# opdracht_1_555_timer.net
KiCad netlist of a schematic drawn in EAGLE
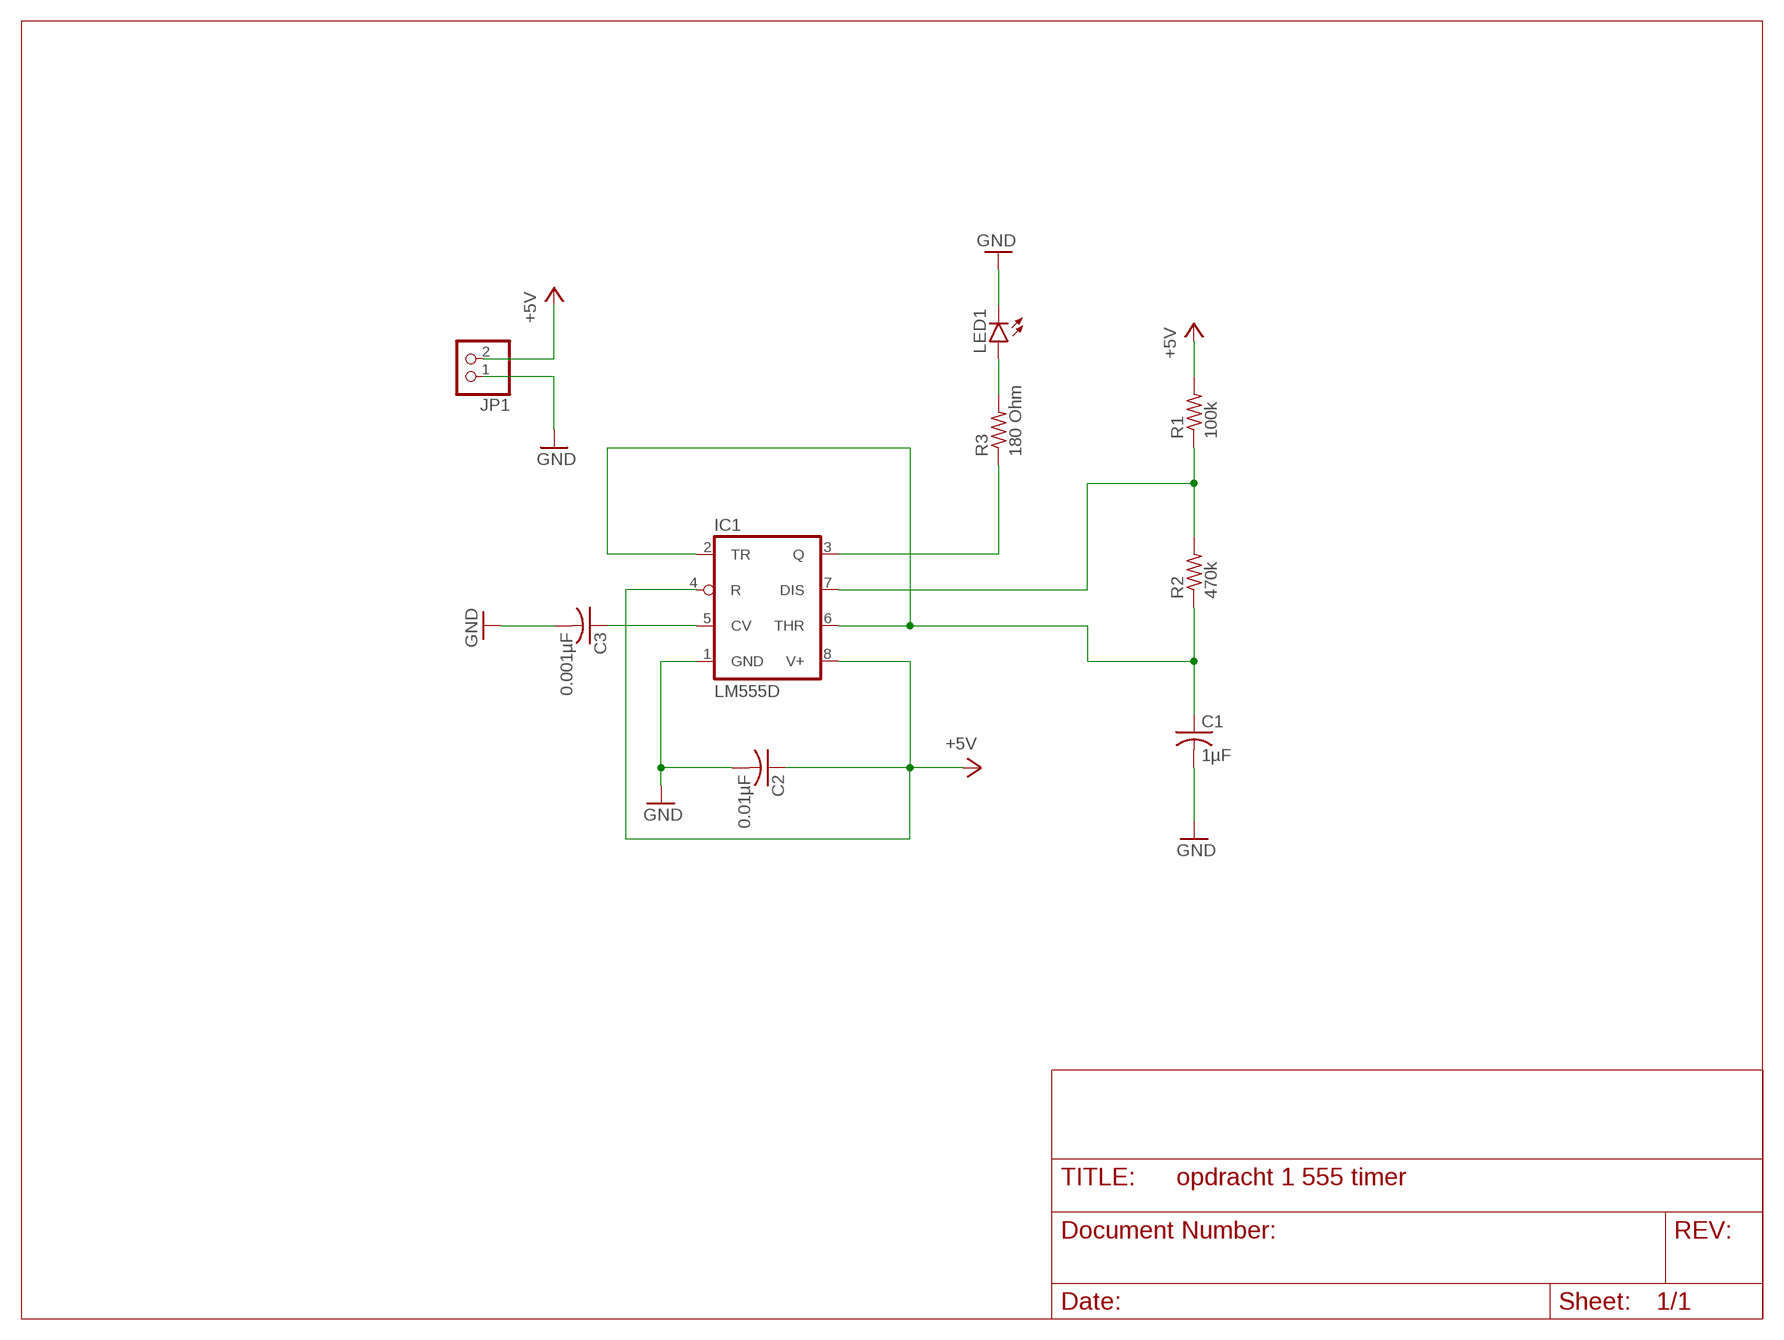
[diagram p0: schematic, sheet 1]

(export (version "E")
  (design (tool "Eeschema 10.0.6"))
  (components
    (comp (ref "C1")
      (value "1µF")
      (footprint "eagle-import:C0805")
      (libsource (lib "eagle-import") (part "C-USC0805"))
    )
    (comp (ref "C2")
      (value "0.01µF")
      (footprint "eagle-import:C0805")
      (libsource (lib "eagle-import") (part "C-USC0805"))
    )
    (comp (ref "C3")
      (value "0.001µF")
      (footprint "eagle-import:C0805")
      (libsource (lib "eagle-import") (part "C-USC0805"))
    )
    (comp (ref "IC1")
      (value "LM555D")
      (footprint "eagle-import:SO08")
      (libsource (lib "eagle-import") (part "555DLM"))
    )
    (comp (ref "JP1")
      (value "PINHD-1X2")
      (footprint "eagle-import:1X02")
      (libsource (lib "eagle-import") (part "PINHD-1X2"))
    )
    (comp (ref "LED1")
      (value "LED5MM")
      (footprint "eagle-import:LED5MM")
      (libsource (lib "eagle-import") (part "LED5MM"))
    )
    (comp (ref "R1")
      (value "100k")
      (footprint "eagle-import:R0805")
      (libsource (lib "eagle-import") (part "R-US_R0805"))
    )
    (comp (ref "R2")
      (value "470k")
      (footprint "eagle-import:R0805")
      (libsource (lib "eagle-import") (part "R-US_R0805"))
    )
    (comp (ref "R3")
      (value "180 Ohm")
      (footprint "eagle-import:R0805")
      (libsource (lib "eagle-import") (part "R-US_R0805"))
    )
  )
  (nets
    (net (code "1") (name "+5V") (class "Default")
      (node (ref "C2") (pin "1") (pinfunction "1_1") (pintype "passive"))
      (node (ref "IC1") (pin "4") (pinfunction "R_4") (pintype "input"))
      (node (ref "IC1") (pin "8") (pinfunction "V+_8") (pintype "power_in"))
      (node (ref "JP1") (pin "2") (pinfunction "2_2") (pintype "passive"))
      (node (ref "R1") (pin "2") (pinfunction "2_2") (pintype "passive"))
    )
    (net (code "2") (name "GND") (class "Default")
      (node (ref "C1") (pin "2") (pinfunction "2_2") (pintype "passive"))
      (node (ref "C2") (pin "2") (pinfunction "2_2") (pintype "passive"))
      (node (ref "C3") (pin "2") (pinfunction "2_2") (pintype "passive"))
      (node (ref "IC1") (pin "1") (pinfunction "GND_1") (pintype "power_in"))
      (node (ref "JP1") (pin "1") (pinfunction "1_1") (pintype "passive"))
      (node (ref "LED1") (pin "K") (pinfunction "C_K") (pintype "passive"))
    )
    (net (code "3") (name "Net-(IC1-CV)") (class "Default")
      (node (ref "C3") (pin "1") (pinfunction "1_1") (pintype "passive"))
      (node (ref "IC1") (pin "5") (pinfunction "CV_5") (pintype "input"))
    )
    (net (code "4") (name "Net-(IC1-DIS)") (class "Default")
      (node (ref "IC1") (pin "7") (pinfunction "DIS_7") (pintype "input"))
      (node (ref "R1") (pin "1") (pinfunction "1_1") (pintype "passive"))
      (node (ref "R2") (pin "2") (pinfunction "2_2") (pintype "passive"))
    )
    (net (code "5") (name "Net-(IC1-Q)") (class "Default")
      (node (ref "IC1") (pin "3") (pinfunction "Q_3") (pintype "output"))
      (node (ref "R3") (pin "1") (pinfunction "1_1") (pintype "passive"))
    )
    (net (code "6") (name "Net-(IC1-THR)") (class "Default")
      (node (ref "C1") (pin "1") (pinfunction "1_1") (pintype "passive"))
      (node (ref "IC1") (pin "2") (pinfunction "TR_2") (pintype "input"))
      (node (ref "IC1") (pin "6") (pinfunction "THR_6") (pintype "input"))
      (node (ref "R2") (pin "1") (pinfunction "1_1") (pintype "passive"))
    )
    (net (code "7") (name "Net-(LED1-PadA)") (class "Default")
      (node (ref "LED1") (pin "A") (pinfunction "A_A") (pintype "passive"))
      (node (ref "R3") (pin "2") (pinfunction "2_2") (pintype "passive"))
    )
  )
)
